# SpiMux.net
KiCad netlist of a schematic drawn in Altium Designer
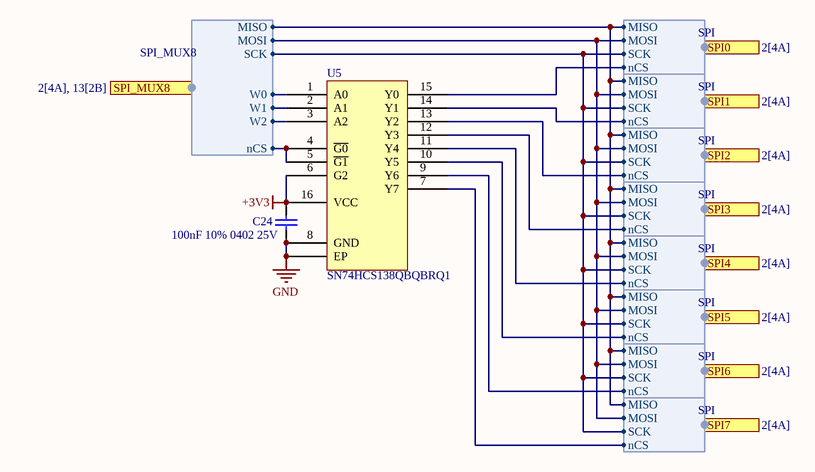
[diagram p0: SpiMux.SchDoc]

(export (version "E")
  (design (tool "Eeschema 10.0.6"))
  (components
    (comp (ref "C24")
      (value "100nF 10% 0402 25V")
      (footprint "0402N")
      (fields (field (name "TOLERANCE") "10") (field (name "VOLTAGE") "25"))
      (libsource (lib "MiscPassives") (part "C0402"))
    )
    (comp (ref "U5")
      (value "SN74HCS138QBQBRQ1")
      (footprint "SN74HCS138QBQBRQ1-Footprint-1")
      (description "Automotive 3-line to 8-line decoders/demultiplexer 16-WQFN -40 to 125")
      (libsource (lib "Saule S.A") (part "SN74HCS138QBQBRQ1"))
    )
  )
  (nets
    (net (code "3") (name "+3V3") (class "Default")
      (node (ref "C24") (pin "2") (pinfunction "2_2") (pintype "passive"))
      (node (ref "U5") (pin "16") (pinfunction "VCC_16") (pintype "passive"))
      (node (ref "U5") (pin "6") (pinfunction "G2_6") (pintype "passive"))
    )
    (net (code "7") (name "/W0") (class "Default")
      (node (ref "U5") (pin "1") (pinfunction "A0_1") (pintype "passive"))
    )
    (net (code "8") (name "/W1") (class "Default")
      (node (ref "U5") (pin "2") (pinfunction "A1_2") (pintype "passive"))
    )
    (net (code "9") (name "/W2") (class "Default")
      (node (ref "U5") (pin "3") (pinfunction "A2_3") (pintype "passive"))
    )
    (net (code "12") (name "GND") (class "Default")
      (node (ref "C24") (pin "1") (pinfunction "1_1") (pintype "passive"))
      (node (ref "U5") (pin "17") (pinfunction "EP_17") (pintype "passive"))
      (node (ref "U5") (pin "8") (pinfunction "GND_8") (pintype "passive"))
    )
    (net (code "13") (name "Net-(U5-~{G0})") (class "Default")
      (node (ref "U5") (pin "4") (pinfunction "~{G0}_4") (pintype "passive"))
      (node (ref "U5") (pin "5") (pinfunction "~{G1}_5") (pintype "passive"))
    )
    (net (code "14") (name "unconnected-(U5-Y0-Pad15)") (class "Default")
      (node (ref "U5") (pin "15") (pinfunction "Y0_15") (pintype "passive"))
    )
    (net (code "15") (name "unconnected-(U5-Y1-Pad14)") (class "Default")
      (node (ref "U5") (pin "14") (pinfunction "Y1_14") (pintype "passive"))
    )
    (net (code "16") (name "unconnected-(U5-Y2-Pad13)") (class "Default")
      (node (ref "U5") (pin "13") (pinfunction "Y2_13") (pintype "passive"))
    )
    (net (code "17") (name "unconnected-(U5-Y3-Pad12)") (class "Default")
      (node (ref "U5") (pin "12") (pinfunction "Y3_12") (pintype "passive"))
    )
    (net (code "18") (name "unconnected-(U5-Y4-Pad11)") (class "Default")
      (node (ref "U5") (pin "11") (pinfunction "Y4_11") (pintype "passive"))
    )
    (net (code "19") (name "unconnected-(U5-Y5-Pad10)") (class "Default")
      (node (ref "U5") (pin "10") (pinfunction "Y5_10") (pintype "passive"))
    )
    (net (code "20") (name "unconnected-(U5-Y6-Pad9)") (class "Default")
      (node (ref "U5") (pin "9") (pinfunction "Y6_9") (pintype "passive"))
    )
    (net (code "21") (name "unconnected-(U5-Y7-Pad7)") (class "Default")
      (node (ref "U5") (pin "7") (pinfunction "Y7_7") (pintype "passive"))
    )
  )
)
